# Contatore_a_relay_3bit_-_Product.net
KiCad netlist of a schematic drawn in EAGLE
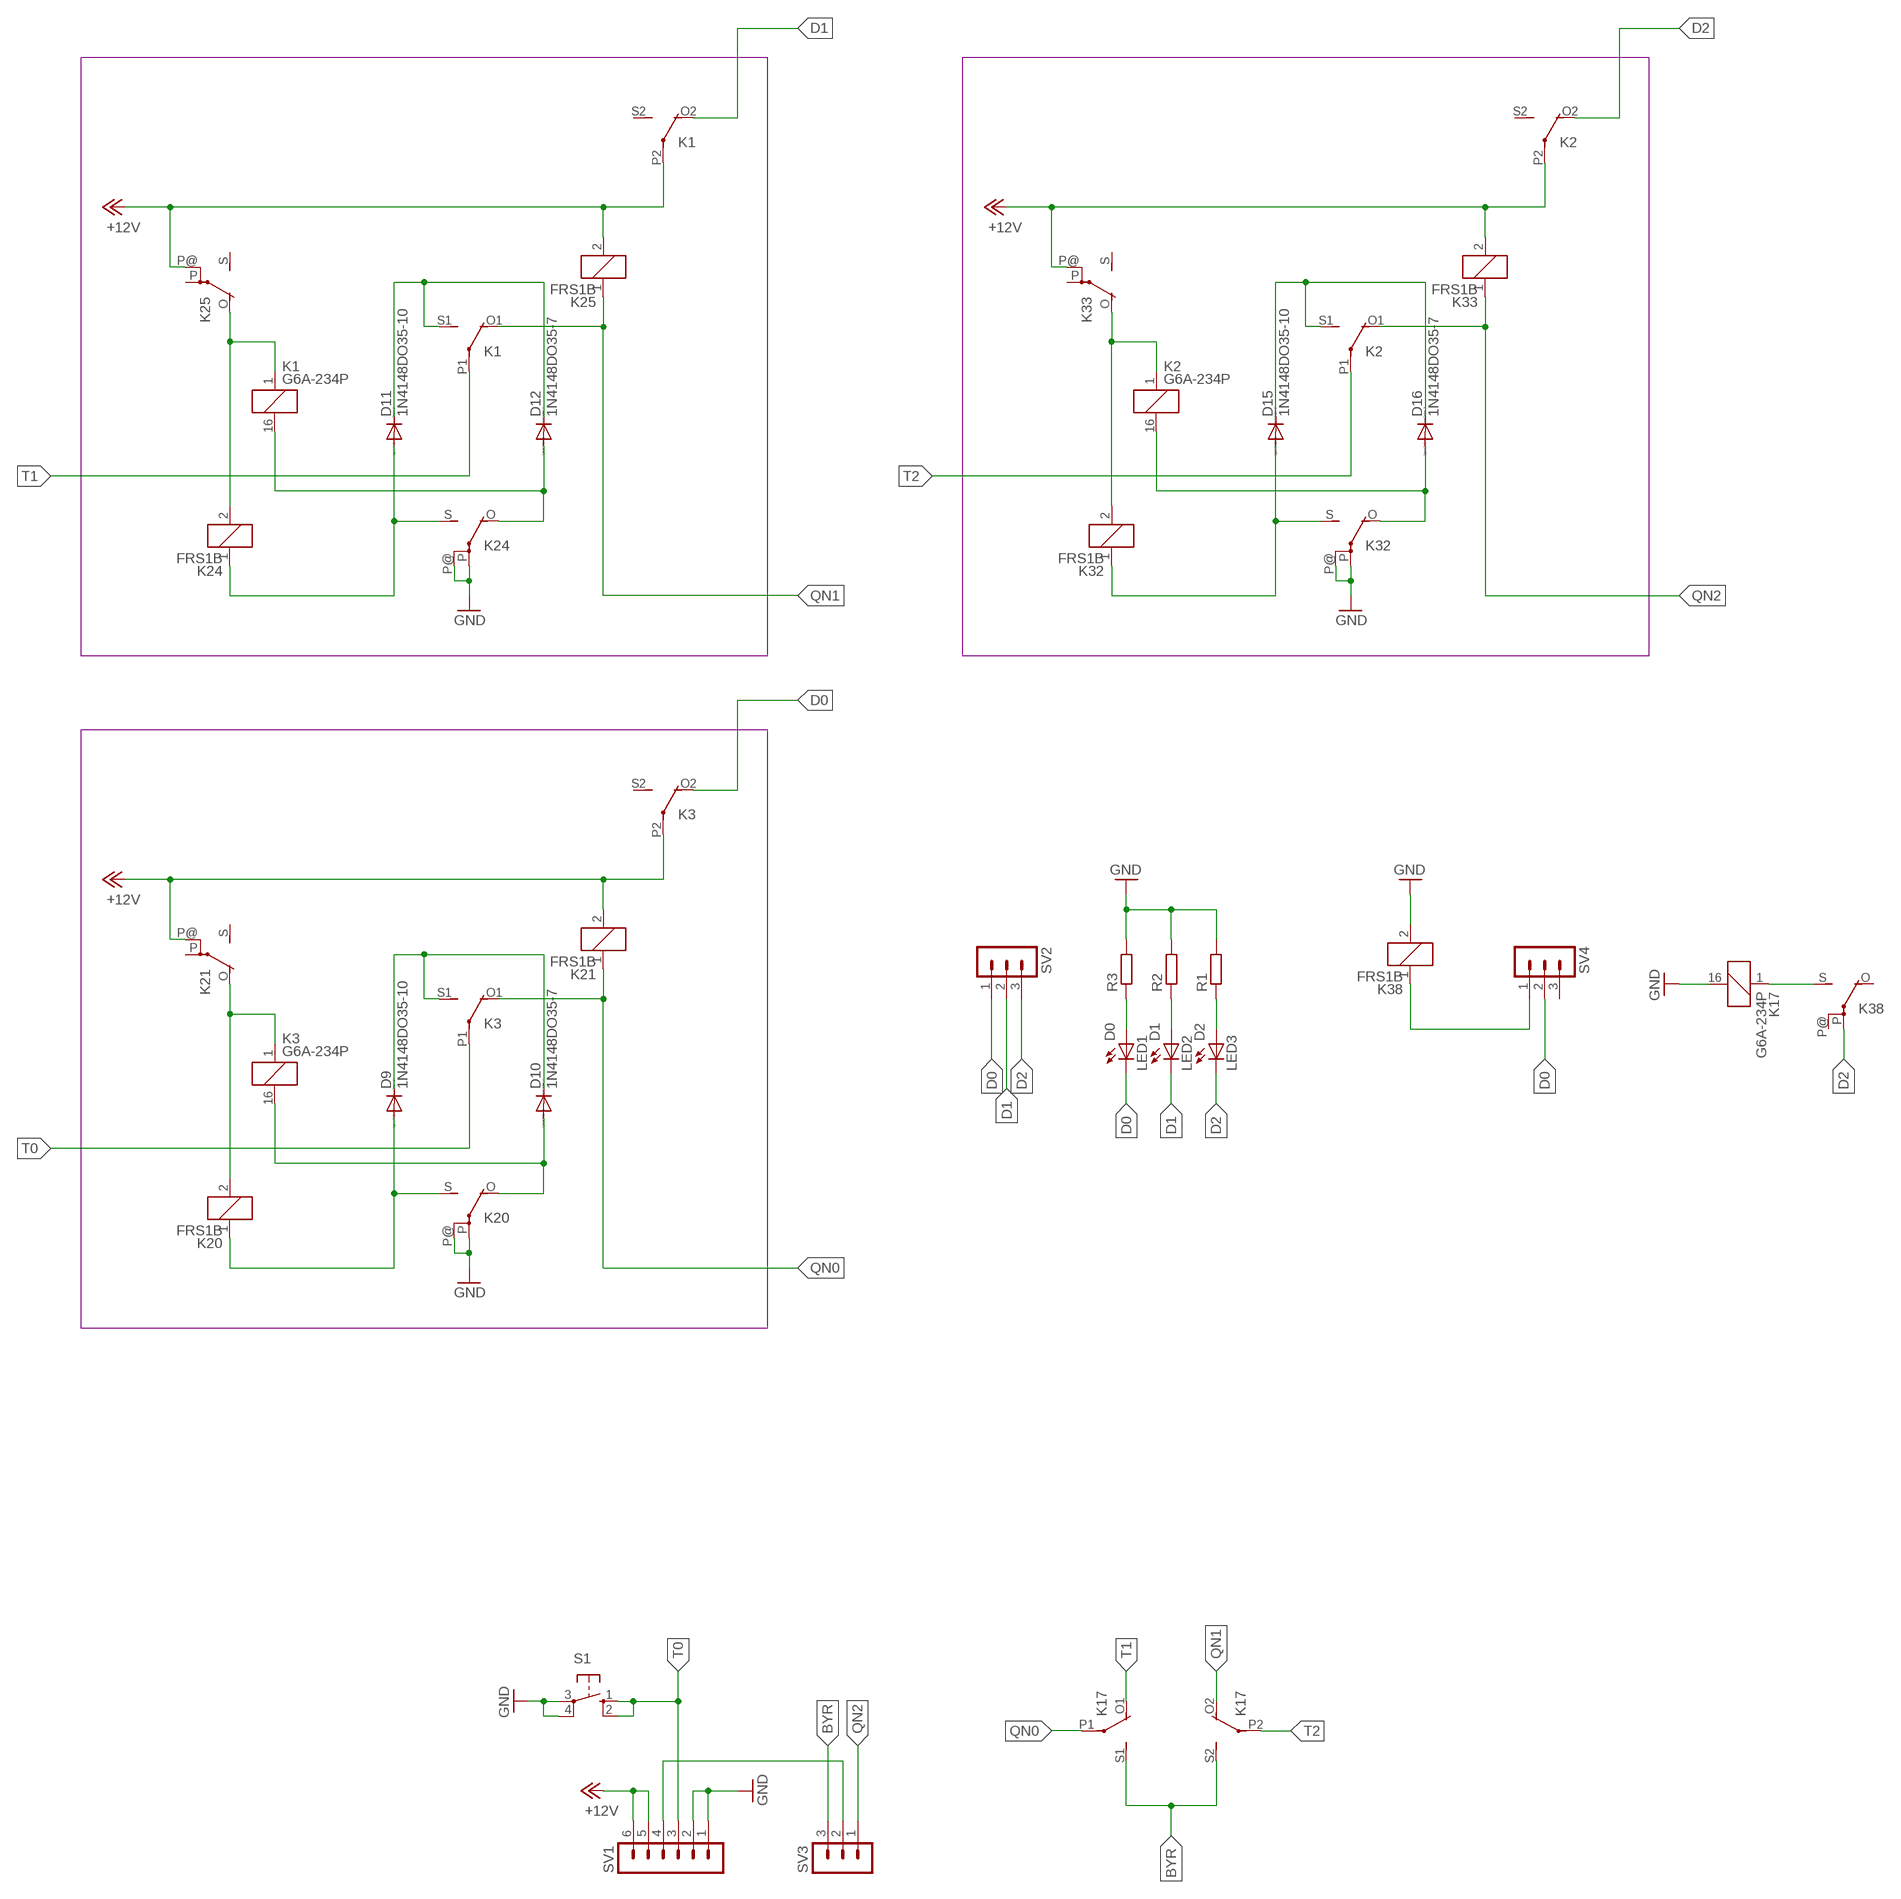
[diagram p0: schematic, sheet 1]

(export (version "E")
  (design (tool "Eeschema 10.0.6"))
  (components
    (comp (ref "D9")
      (value "1N4148DO35-10")
      (footprint "eagle-import:DO35-10")
      (libsource (lib "eagle-import") (part "1N4148DO35-10"))
    )
    (comp (ref "D10")
      (value "1N4148DO35-7")
      (footprint "eagle-import:DO35-7")
      (libsource (lib "eagle-import") (part "1N4148DO35-7"))
    )
    (comp (ref "D11")
      (value "1N4148DO35-10")
      (footprint "eagle-import:DO35-10")
      (libsource (lib "eagle-import") (part "1N4148DO35-10"))
    )
    (comp (ref "D12")
      (value "1N4148DO35-7")
      (footprint "eagle-import:DO35-7")
      (libsource (lib "eagle-import") (part "1N4148DO35-7"))
    )
    (comp (ref "D15")
      (value "1N4148DO35-10")
      (footprint "eagle-import:DO35-10")
      (libsource (lib "eagle-import") (part "1N4148DO35-10"))
    )
    (comp (ref "D16")
      (value "1N4148DO35-7")
      (footprint "eagle-import:DO35-7")
      (libsource (lib "eagle-import") (part "1N4148DO35-7"))
    )
    (comp (ref "K1")
      (value "G6A-234P")
      (footprint "eagle-import:G6A-234P")
      (libsource (lib "eagle-import") (part "G6A-234P"))
    )
    (comp (ref "K2")
      (value "G6A-234P")
      (footprint "eagle-import:G6A-234P")
      (libsource (lib "eagle-import") (part "G6A-234P"))
    )
    (comp (ref "K3")
      (value "G6A-234P")
      (footprint "eagle-import:G6A-234P")
      (libsource (lib "eagle-import") (part "G6A-234P"))
    )
    (comp (ref "K17")
      (value "G6A-234P")
      (footprint "eagle-import:G6A-234P")
      (libsource (lib "eagle-import") (part "G6A-234P"))
    )
    (comp (ref "K20")
      (value "FRS1B")
      (footprint "eagle-import:FRS1B")
      (libsource (lib "eagle-import") (part "FRS1B"))
    )
    (comp (ref "K21")
      (value "FRS1B")
      (footprint "eagle-import:FRS1B")
      (libsource (lib "eagle-import") (part "FRS1B"))
    )
    (comp (ref "K24")
      (value "FRS1B")
      (footprint "eagle-import:FRS1B")
      (libsource (lib "eagle-import") (part "FRS1B"))
    )
    (comp (ref "K25")
      (value "FRS1B")
      (footprint "eagle-import:FRS1B")
      (libsource (lib "eagle-import") (part "FRS1B"))
    )
    (comp (ref "K32")
      (value "FRS1B")
      (footprint "eagle-import:FRS1B")
      (libsource (lib "eagle-import") (part "FRS1B"))
    )
    (comp (ref "K33")
      (value "FRS1B")
      (footprint "eagle-import:FRS1B")
      (libsource (lib "eagle-import") (part "FRS1B"))
    )
    (comp (ref "K38")
      (value "FRS1B")
      (footprint "eagle-import:FRS1B")
      (libsource (lib "eagle-import") (part "FRS1B"))
    )
    (comp (ref "LED1")
      (value "D0")
      (footprint "eagle-import:LED3MM")
      (libsource (lib "eagle-import") (part "LED3MM"))
    )
    (comp (ref "LED2")
      (value "D1")
      (footprint "eagle-import:LED3MM")
      (libsource (lib "eagle-import") (part "LED3MM"))
    )
    (comp (ref "LED3")
      (value "D2")
      (footprint "eagle-import:LED3MM")
      (libsource (lib "eagle-import") (part "LED3MM"))
    )
    (comp (ref "R1")
      (value "R-EU_M0805")
      (footprint "eagle-import:M0805")
      (libsource (lib "eagle-import") (part "R-EU_M0805"))
    )
    (comp (ref "R2")
      (value "R-EU_M0805")
      (footprint "eagle-import:M0805")
      (libsource (lib "eagle-import") (part "R-EU_M0805"))
    )
    (comp (ref "R3")
      (value "R-EU_M0805")
      (footprint "eagle-import:M0805")
      (libsource (lib "eagle-import") (part "R-EU_M0805"))
    )
    (comp (ref "S1")
      (value "10-XX")
      (footprint "eagle-import:B3F-10XX")
      (fields (field (name "MPN") "B3F-1000"))
      (libsource (lib "eagle-import") (part "10-XX"))
    )
    (comp (ref "SV1")
      (value "MA06-1")
      (footprint "eagle-import:MA06-1")
      (libsource (lib "eagle-import") (part "MA06-1"))
    )
    (comp (ref "SV2")
      (value "MA03-1")
      (footprint "eagle-import:MA03-1")
      (libsource (lib "eagle-import") (part "MA03-1"))
    )
    (comp (ref "SV3")
      (value "MA03-1")
      (footprint "eagle-import:MA03-1")
      (libsource (lib "eagle-import") (part "MA03-1"))
    )
    (comp (ref "SV4")
      (value "MA03-1")
      (footprint "eagle-import:MA03-1")
      (libsource (lib "eagle-import") (part "MA03-1"))
    )
  )
  (nets
    (net (code "1") (name "+12V") (class "Default")
      (node (ref "K1") (pin "P2") (pinfunction "P_P2") (pintype "passive"))
      (node (ref "K2") (pin "P2") (pinfunction "P_P2") (pintype "passive"))
      (node (ref "K21") (pin "2") (pinfunction "2_2") (pintype "passive"))
      (node (ref "K21") (pin "P@") (pinfunction "P_P@") (pintype "passive"))
      (node (ref "K25") (pin "2") (pinfunction "2_2") (pintype "passive"))
      (node (ref "K25") (pin "P@") (pinfunction "P_P@") (pintype "passive"))
      (node (ref "K3") (pin "P2") (pinfunction "P_P2") (pintype "passive"))
      (node (ref "K33") (pin "2") (pinfunction "2_2") (pintype "passive"))
      (node (ref "K33") (pin "P@") (pinfunction "P_P@") (pintype "passive"))
      (node (ref "SV1") (pin "5") (pinfunction "5_5") (pintype "passive"))
      (node (ref "SV1") (pin "6") (pinfunction "6_6") (pintype "passive"))
    )
    (net (code "2") (name "BYR") (class "Default")
      (node (ref "K17") (pin "S1") (pinfunction "S_S1") (pintype "passive"))
      (node (ref "K17") (pin "S2") (pinfunction "S_S2") (pintype "passive"))
      (node (ref "SV3") (pin "3") (pinfunction "3_3") (pintype "passive"))
    )
    (net (code "3") (name "D0") (class "Default")
      (node (ref "K3") (pin "O2") (pinfunction "O_O2") (pintype "passive"))
      (node (ref "LED1") (pin "K") (pinfunction "C_K") (pintype "passive"))
      (node (ref "SV2") (pin "1") (pinfunction "1_1") (pintype "passive"))
      (node (ref "SV4") (pin "2") (pinfunction "2_2") (pintype "passive"))
    )
    (net (code "4") (name "D1") (class "Default")
      (node (ref "K1") (pin "O2") (pinfunction "O_O2") (pintype "passive"))
      (node (ref "LED2") (pin "K") (pinfunction "C_K") (pintype "passive"))
      (node (ref "SV2") (pin "2") (pinfunction "2_2") (pintype "passive"))
    )
    (net (code "5") (name "D2") (class "Default")
      (node (ref "K2") (pin "O2") (pinfunction "O_O2") (pintype "passive"))
      (node (ref "K38") (pin "P") (pinfunction "P_P") (pintype "passive"))
      (node (ref "LED3") (pin "K") (pinfunction "C_K") (pintype "passive"))
      (node (ref "SV2") (pin "3") (pinfunction "3_3") (pintype "passive"))
    )
    (net (code "6") (name "GND") (class "Default")
      (node (ref "K17") (pin "16") (pinfunction "2_16") (pintype "passive"))
      (node (ref "K20") (pin "P") (pinfunction "P_P") (pintype "passive"))
      (node (ref "K20") (pin "P@") (pinfunction "P_P@") (pintype "passive"))
      (node (ref "K24") (pin "P") (pinfunction "P_P") (pintype "passive"))
      (node (ref "K24") (pin "P@") (pinfunction "P_P@") (pintype "passive"))
      (node (ref "K32") (pin "P") (pinfunction "P_P") (pintype "passive"))
      (node (ref "K32") (pin "P@") (pinfunction "P_P@") (pintype "passive"))
      (node (ref "K38") (pin "2") (pinfunction "2_2") (pintype "passive"))
      (node (ref "R1") (pin "2") (pinfunction "2_2") (pintype "passive"))
      (node (ref "R2") (pin "2") (pinfunction "2_2") (pintype "passive"))
      (node (ref "R3") (pin "2") (pinfunction "2_2") (pintype "passive"))
      (node (ref "S1") (pin "3") (pinfunction "P_3") (pintype "passive"))
      (node (ref "S1") (pin "4") (pinfunction "P1_4") (pintype "passive"))
      (node (ref "SV1") (pin "1") (pinfunction "1_1") (pintype "passive"))
      (node (ref "SV1") (pin "2") (pinfunction "2_2") (pintype "passive"))
    )
    (net (code "7") (name "Net-(D9-PadA)") (class "Default")
      (node (ref "D9") (pin "A") (pinfunction "A_A") (pintype "passive"))
      (node (ref "K20") (pin "1") (pinfunction "1_1") (pintype "passive"))
      (node (ref "K20") (pin "S") (pinfunction "S_S") (pintype "passive"))
    )
    (net (code "8") (name "Net-(D11-PadA)") (class "Default")
      (node (ref "D11") (pin "A") (pinfunction "A_A") (pintype "passive"))
      (node (ref "K24") (pin "1") (pinfunction "1_1") (pintype "passive"))
      (node (ref "K24") (pin "S") (pinfunction "S_S") (pintype "passive"))
    )
    (net (code "9") (name "Net-(D15-PadA)") (class "Default")
      (node (ref "D15") (pin "A") (pinfunction "A_A") (pintype "passive"))
      (node (ref "K32") (pin "1") (pinfunction "1_1") (pintype "passive"))
      (node (ref "K32") (pin "S") (pinfunction "S_S") (pintype "passive"))
    )
    (net (code "10") (name "Net-(K1-Pad1)") (class "Default")
      (node (ref "K1") (pin "1") (pinfunction "1_1") (pintype "passive"))
      (node (ref "K24") (pin "2") (pinfunction "2_2") (pintype "passive"))
      (node (ref "K25") (pin "O") (pinfunction "O_O") (pintype "passive"))
    )
    (net (code "11") (name "Net-(K1A-2)") (class "Default")
      (node (ref "D12") (pin "A") (pinfunction "A_A") (pintype "passive"))
      (node (ref "K1") (pin "16") (pinfunction "2_16") (pintype "passive"))
      (node (ref "K24") (pin "O") (pinfunction "O_O") (pintype "passive"))
    )
    (net (code "12") (name "Net-(K1B-S)") (class "Default")
      (node (ref "D11") (pin "C") (pinfunction "C_C") (pintype "passive"))
      (node (ref "D12") (pin "C") (pinfunction "C_C") (pintype "passive"))
      (node (ref "K1") (pin "S1") (pinfunction "S_S1") (pintype "passive"))
    )
    (net (code "13") (name "Net-(K2-Pad1)") (class "Default")
      (node (ref "K2") (pin "1") (pinfunction "1_1") (pintype "passive"))
      (node (ref "K32") (pin "2") (pinfunction "2_2") (pintype "passive"))
      (node (ref "K33") (pin "O") (pinfunction "O_O") (pintype "passive"))
    )
    (net (code "14") (name "Net-(K2A-2)") (class "Default")
      (node (ref "D16") (pin "A") (pinfunction "A_A") (pintype "passive"))
      (node (ref "K2") (pin "16") (pinfunction "2_16") (pintype "passive"))
      (node (ref "K32") (pin "O") (pinfunction "O_O") (pintype "passive"))
    )
    (net (code "15") (name "Net-(K2B-S)") (class "Default")
      (node (ref "D15") (pin "C") (pinfunction "C_C") (pintype "passive"))
      (node (ref "D16") (pin "C") (pinfunction "C_C") (pintype "passive"))
      (node (ref "K2") (pin "S1") (pinfunction "S_S1") (pintype "passive"))
    )
    (net (code "16") (name "Net-(K3A-2)") (class "Default")
      (node (ref "D10") (pin "A") (pinfunction "A_A") (pintype "passive"))
      (node (ref "K20") (pin "O") (pinfunction "O_O") (pintype "passive"))
      (node (ref "K3") (pin "16") (pinfunction "2_16") (pintype "passive"))
    )
    (net (code "17") (name "Net-(K3B-S)") (class "Default")
      (node (ref "D10") (pin "C") (pinfunction "C_C") (pintype "passive"))
      (node (ref "D9") (pin "C") (pinfunction "C_C") (pintype "passive"))
      (node (ref "K3") (pin "S1") (pinfunction "S_S1") (pintype "passive"))
    )
    (net (code "18") (name "Net-(K17-Pad1)") (class "Default")
      (node (ref "K17") (pin "1") (pinfunction "1_1") (pintype "passive"))
      (node (ref "K38") (pin "S") (pinfunction "S_S") (pintype "passive"))
    )
    (net (code "19") (name "Net-(K20-Pad2)") (class "Default")
      (node (ref "K20") (pin "2") (pinfunction "2_2") (pintype "passive"))
      (node (ref "K21") (pin "O") (pinfunction "O_O") (pintype "passive"))
      (node (ref "K3") (pin "1") (pinfunction "1_1") (pintype "passive"))
    )
    (net (code "20") (name "Net-(K38-Pad1)") (class "Default")
      (node (ref "K38") (pin "1") (pinfunction "1_1") (pintype "passive"))
      (node (ref "SV4") (pin "1") (pinfunction "1_1") (pintype "passive"))
    )
    (net (code "21") (name "Net-(LED1-PadA)") (class "Default")
      (node (ref "LED1") (pin "A") (pinfunction "A_A") (pintype "passive"))
      (node (ref "R3") (pin "1") (pinfunction "1_1") (pintype "passive"))
    )
    (net (code "22") (name "Net-(LED2-PadA)") (class "Default")
      (node (ref "LED2") (pin "A") (pinfunction "A_A") (pintype "passive"))
      (node (ref "R2") (pin "1") (pinfunction "1_1") (pintype "passive"))
    )
    (net (code "23") (name "Net-(LED3-PadA)") (class "Default")
      (node (ref "LED3") (pin "A") (pinfunction "A_A") (pintype "passive"))
      (node (ref "R1") (pin "1") (pinfunction "1_1") (pintype "passive"))
    )
    (net (code "24") (name "Net-(SV1-Pad4)") (class "Default")
      (node (ref "SV1") (pin "4") (pinfunction "4_4") (pintype "passive"))
      (node (ref "SV3") (pin "2") (pinfunction "2_2") (pintype "passive"))
    )
    (net (code "25") (name "QN0") (class "Default")
      (node (ref "K17") (pin "P1") (pinfunction "P_P1") (pintype "passive"))
      (node (ref "K21") (pin "1") (pinfunction "1_1") (pintype "passive"))
      (node (ref "K3") (pin "O1") (pinfunction "O_O1") (pintype "passive"))
    )
    (net (code "26") (name "QN1") (class "Default")
      (node (ref "K1") (pin "O1") (pinfunction "O_O1") (pintype "passive"))
      (node (ref "K17") (pin "O2") (pinfunction "O_O2") (pintype "passive"))
      (node (ref "K25") (pin "1") (pinfunction "1_1") (pintype "passive"))
    )
    (net (code "27") (name "QN2") (class "Default")
      (node (ref "K2") (pin "O1") (pinfunction "O_O1") (pintype "passive"))
      (node (ref "K33") (pin "1") (pinfunction "1_1") (pintype "passive"))
      (node (ref "SV3") (pin "1") (pinfunction "1_1") (pintype "passive"))
    )
    (net (code "28") (name "T0") (class "Default")
      (node (ref "K3") (pin "P1") (pinfunction "P_P1") (pintype "passive"))
      (node (ref "S1") (pin "1") (pinfunction "S_1") (pintype "passive"))
      (node (ref "S1") (pin "2") (pinfunction "S1_2") (pintype "passive"))
      (node (ref "SV1") (pin "3") (pinfunction "3_3") (pintype "passive"))
    )
    (net (code "29") (name "T1") (class "Default")
      (node (ref "K1") (pin "P1") (pinfunction "P_P1") (pintype "passive"))
      (node (ref "K17") (pin "O1") (pinfunction "O_O1") (pintype "passive"))
    )
    (net (code "30") (name "T2") (class "Default")
      (node (ref "K17") (pin "P2") (pinfunction "P_P2") (pintype "passive"))
      (node (ref "K2") (pin "P1") (pinfunction "P_P1") (pintype "passive"))
    )
    (net (code "31") (name "unconnected-(K1C-S-PadS2)") (class "Default")
      (node (ref "K1") (pin "S2") (pinfunction "S_S2") (pintype "passive"))
    )
    (net (code "32") (name "unconnected-(K2C-S-PadS2)") (class "Default")
      (node (ref "K2") (pin "S2") (pinfunction "S_S2") (pintype "passive"))
    )
    (net (code "33") (name "unconnected-(K3C-S-PadS2)") (class "Default")
      (node (ref "K3") (pin "S2") (pinfunction "S_S2") (pintype "passive"))
    )
    (net (code "34") (name "unconnected-(K21-PadP)") (class "Default")
      (node (ref "K21") (pin "P") (pinfunction "P_P") (pintype "passive"))
    )
    (net (code "35") (name "unconnected-(K21-PadS)") (class "Default")
      (node (ref "K21") (pin "S") (pinfunction "S_S") (pintype "passive"))
    )
    (net (code "36") (name "unconnected-(K25-PadP)") (class "Default")
      (node (ref "K25") (pin "P") (pinfunction "P_P") (pintype "passive"))
    )
    (net (code "37") (name "unconnected-(K25-PadS)") (class "Default")
      (node (ref "K25") (pin "S") (pinfunction "S_S") (pintype "passive"))
    )
    (net (code "38") (name "unconnected-(K33-PadP)") (class "Default")
      (node (ref "K33") (pin "P") (pinfunction "P_P") (pintype "passive"))
    )
    (net (code "39") (name "unconnected-(K33-PadS)") (class "Default")
      (node (ref "K33") (pin "S") (pinfunction "S_S") (pintype "passive"))
    )
    (net (code "40") (name "unconnected-(K38-PadO)") (class "Default")
      (node (ref "K38") (pin "O") (pinfunction "O_O") (pintype "passive"))
    )
    (net (code "41") (name "unconnected-(K38B-P-PadP@)") (class "Default")
      (node (ref "K38") (pin "P@") (pinfunction "P_P@") (pintype "passive"))
    )
    (net (code "42") (name "unconnected-(SV4-Pad3)") (class "Default")
      (node (ref "SV4") (pin "3") (pinfunction "3_3") (pintype "passive"))
    )
  )
)
